# SCH.net
KiCad netlist of a schematic drawn in Altium Designer
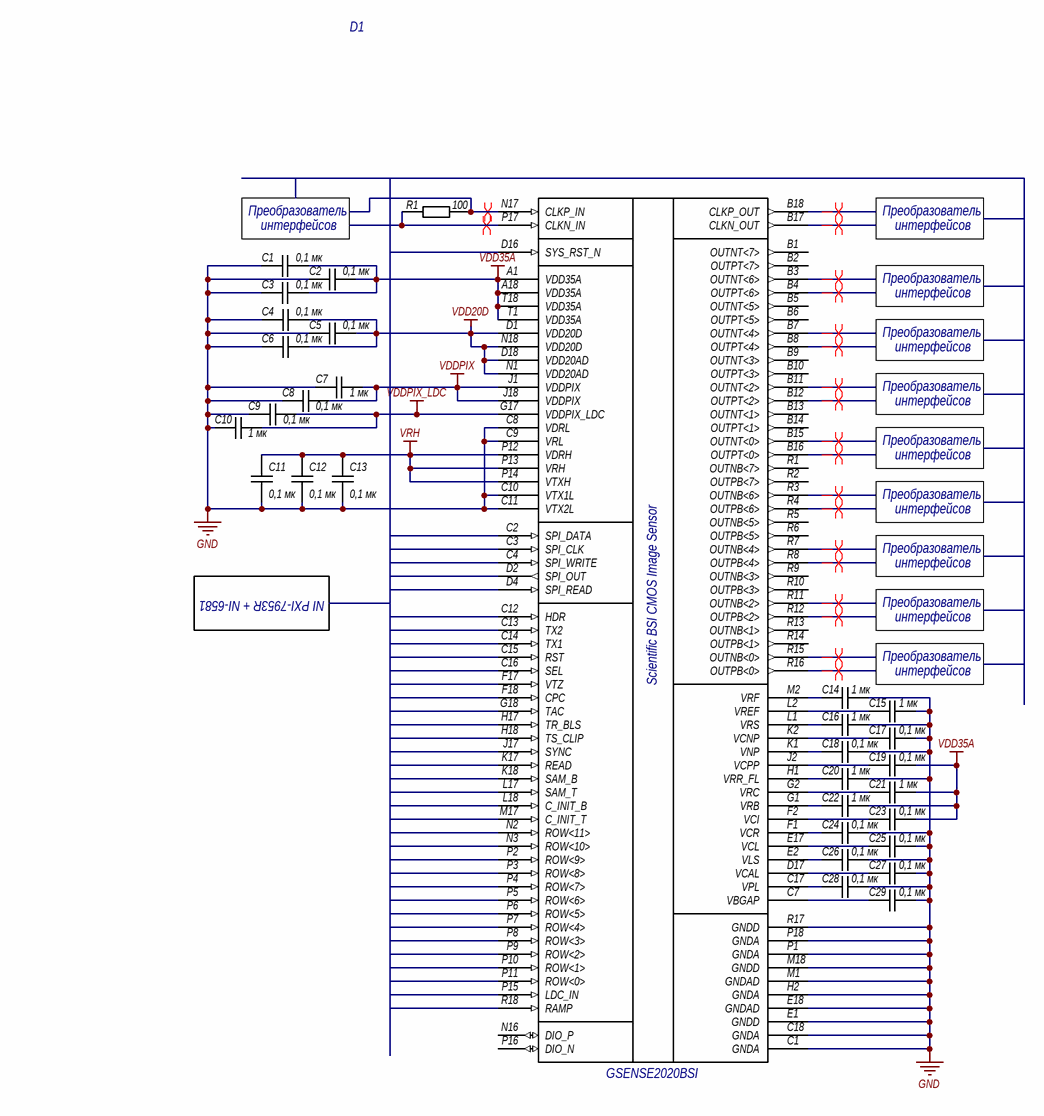
[diagram p0: SCH.SchDoc]

(export (version "E")
  (design (tool "Eeschema 10.0.6"))
  (components
    (comp (ref "C1") (value "0,1 мк") (description "Capacitor") (libsource (lib "VPL") (part "Cap")))
    (comp (ref "C2") (value "0,1 мк") (description "Capacitor") (libsource (lib "VPL") (part "Cap")))
    (comp (ref "C3") (value "0,1 мк") (description "Capacitor") (libsource (lib "VPL") (part "Cap")))
    (comp (ref "C4") (value "0,1 мк") (description "Capacitor") (libsource (lib "VPL") (part "Cap")))
    (comp (ref "C5") (value "0,1 мк") (description "Capacitor") (libsource (lib "VPL") (part "Cap")))
    (comp (ref "C6") (value "0,1 мк") (description "Capacitor") (libsource (lib "VPL") (part "Cap")))
    (comp (ref "C7") (value "1 мк") (description "Capacitor") (libsource (lib "VPL") (part "Cap")))
    (comp (ref "C8") (value "0,1 мк") (description "Capacitor") (libsource (lib "VPL") (part "Cap")))
    (comp (ref "C9") (value "0,1 мк") (description "Capacitor") (libsource (lib "VPL") (part "Cap")))
    (comp (ref "C10") (value "1 мк") (description "Capacitor") (libsource (lib "VPL") (part "Cap")))
    (comp (ref "C11") (value "0,1 мк") (description "Capacitor") (libsource (lib "VPL") (part "Cap")))
    (comp (ref "C12") (value "0,1 мк") (description "Capacitor") (libsource (lib "VPL") (part "Cap")))
    (comp (ref "C13") (value "0,1 мк") (description "Capacitor") (libsource (lib "VPL") (part "Cap")))
    (comp (ref "C14") (value "1 мк") (description "Capacitor") (libsource (lib "VPL") (part "Cap")))
    (comp (ref "C15") (value "1 мк") (description "Capacitor") (libsource (lib "VPL") (part "Cap")))
    (comp (ref "C16") (value "1 мк") (description "Capacitor") (libsource (lib "VPL") (part "Cap")))
    (comp (ref "C17") (value "0,1 мк") (description "Capacitor") (libsource (lib "VPL") (part "Cap")))
    (comp (ref "C18") (value "0,1 мк") (description "Capacitor") (libsource (lib "VPL") (part "Cap")))
    (comp (ref "C19") (value "0,1 мк") (description "Capacitor") (libsource (lib "VPL") (part "Cap")))
    (comp (ref "C20") (value "1 мк") (description "Capacitor") (libsource (lib "VPL") (part "Cap")))
    (comp (ref "C21") (value "1 мк") (description "Capacitor") (libsource (lib "VPL") (part "Cap")))
    (comp (ref "C22") (value "1 мк") (description "Capacitor") (libsource (lib "VPL") (part "Cap")))
    (comp (ref "C23") (value "0,1 мк") (description "Capacitor") (libsource (lib "VPL") (part "Cap")))
    (comp (ref "C24") (value "0,1 мк") (description "Capacitor") (libsource (lib "VPL") (part "Cap")))
    (comp (ref "C25") (value "0,1 мк") (description "Capacitor") (libsource (lib "VPL") (part "Cap")))
    (comp (ref "C26") (value "0,1 мк") (description "Capacitor") (libsource (lib "VPL") (part "Cap")))
    (comp (ref "C27") (value "0,1 мк") (description "Capacitor") (libsource (lib "VPL") (part "Cap")))
    (comp (ref "C28") (value "0,1 мк") (description "Capacitor") (libsource (lib "VPL") (part "Cap")))
    (comp (ref "C29") (value "0,1 мк") (description "Capacitor") (libsource (lib "VPL") (part "Cap")))
    (comp (ref "D1")
      (value "GSENSE2020BSI")
      (footprint "GSENSE2020BSI")
      (libsource (lib "Schlib") (part "GSENSE2020BSI"))
    )
    (comp (ref "R1")
      (value "100")
      (footprint "RES")
      (description "Resistor")
      (libsource (lib "VPL") (part "Res"))
    )
  )
  (nets
    (net (code "1") (name "GND") (class "Default")
      (node (ref "C1") (pin "2") (pintype "passive"))
      (node (ref "C10") (pin "2") (pintype "passive"))
      (node (ref "C11") (pin "1") (pintype "passive"))
      (node (ref "C12") (pin "1") (pintype "passive"))
      (node (ref "C13") (pin "1") (pintype "passive"))
      (node (ref "C14") (pin "2") (pintype "passive"))
      (node (ref "C15") (pin "2") (pintype "passive"))
      (node (ref "C16") (pin "2") (pintype "passive"))
      (node (ref "C17") (pin "2") (pintype "passive"))
      (node (ref "C18") (pin "2") (pintype "passive"))
      (node (ref "C2") (pin "2") (pintype "passive"))
      (node (ref "C20") (pin "2") (pintype "passive"))
      (node (ref "C24") (pin "2") (pintype "passive"))
      (node (ref "C25") (pin "2") (pintype "passive"))
      (node (ref "C26") (pin "2") (pintype "passive"))
      (node (ref "C27") (pin "2") (pintype "passive"))
      (node (ref "C28") (pin "2") (pintype "passive"))
      (node (ref "C29") (pin "2") (pintype "passive"))
      (node (ref "C3") (pin "2") (pintype "passive"))
      (node (ref "C4") (pin "2") (pintype "passive"))
      (node (ref "C5") (pin "2") (pintype "passive"))
      (node (ref "C6") (pin "2") (pintype "passive"))
      (node (ref "C7") (pin "2") (pintype "passive"))
      (node (ref "C8") (pin "2") (pintype "passive"))
      (node (ref "C9") (pin "2") (pintype "passive"))
      (node (ref "D1") (pin "C1") (pinfunction "GNDA_C1") (pintype "passive"))
      (node (ref "D1") (pin "C10") (pinfunction "VTX1L_C10") (pintype "passive"))
      (node (ref "D1") (pin "C11") (pinfunction "VTX2L_C11") (pintype "passive"))
      (node (ref "D1") (pin "C18") (pinfunction "GNDA_C18") (pintype "passive"))
      (node (ref "D1") (pin "C8") (pinfunction "VDRL_C8") (pintype "passive"))
      (node (ref "D1") (pin "C9") (pinfunction "VRL_C9") (pintype "passive"))
      (node (ref "D1") (pin "E1") (pinfunction "GNDD_E1") (pintype "passive"))
      (node (ref "D1") (pin "E18") (pinfunction "GNDAD_E18") (pintype "passive"))
      (node (ref "D1") (pin "H2") (pinfunction "GNDA_H2") (pintype "passive"))
      (node (ref "D1") (pin "M1") (pinfunction "GNDAD_M1") (pintype "passive"))
      (node (ref "D1") (pin "M18") (pinfunction "GNDD_M18") (pintype "passive"))
      (node (ref "D1") (pin "P1") (pinfunction "GNDA_P1") (pintype "passive"))
      (node (ref "D1") (pin "P18") (pinfunction "GNDA_P18") (pintype "passive"))
      (node (ref "D1") (pin "R17") (pinfunction "GNDD_R17") (pintype "passive"))
    )
    (net (code "2") (name "Net-(D1-CLKN_IN)") (class "Default")
      (node (ref "D1") (pin "P17") (pinfunction "CLKN_IN_P17") (pintype "input"))
      (node (ref "R1") (pin "2") (pintype "passive"))
    )
    (net (code "3") (name "Net-(D1-CLKP_IN)") (class "Default")
      (node (ref "D1") (pin "N17") (pinfunction "CLKP_IN_N17") (pintype "input"))
      (node (ref "R1") (pin "1") (pintype "passive"))
    )
    (net (code "4") (name "Net-(D1-VBGAP)") (class "Default")
      (node (ref "C29") (pin "1") (pintype "passive"))
      (node (ref "D1") (pin "C7") (pinfunction "VBGAP_C7") (pintype "passive"))
    )
    (net (code "5") (name "Net-(D1-VCAL)") (class "Default")
      (node (ref "C27") (pin "1") (pintype "passive"))
      (node (ref "D1") (pin "D17") (pinfunction "VCAL_D17") (pintype "passive"))
    )
    (net (code "6") (name "Net-(D1-VCI)") (class "Default")
      (node (ref "C23") (pin "1") (pintype "passive"))
      (node (ref "D1") (pin "F2") (pinfunction "VCI_F2") (pintype "passive"))
    )
    (net (code "7") (name "Net-(D1-VCL)") (class "Default")
      (node (ref "C25") (pin "1") (pintype "passive"))
      (node (ref "D1") (pin "E17") (pinfunction "VCL_E17") (pintype "passive"))
    )
    (net (code "8") (name "Net-(D1-VCNP)") (class "Default")
      (node (ref "C17") (pin "1") (pintype "passive"))
      (node (ref "D1") (pin "K2") (pinfunction "VCNP_K2") (pintype "passive"))
    )
    (net (code "9") (name "Net-(D1-VCPP)") (class "Default")
      (node (ref "C19") (pin "1") (pintype "passive"))
      (node (ref "D1") (pin "J2") (pinfunction "VCPP_J2") (pintype "passive"))
    )
    (net (code "10") (name "Net-(D1-VCR)") (class "Default")
      (node (ref "C24") (pin "1") (pintype "passive"))
      (node (ref "D1") (pin "F1") (pinfunction "VCR_F1") (pintype "passive"))
    )
    (net (code "11") (name "Net-(D1-VLS)") (class "Default")
      (node (ref "C26") (pin "1") (pintype "passive"))
      (node (ref "D1") (pin "E2") (pinfunction "VLS_E2") (pintype "passive"))
    )
    (net (code "12") (name "Net-(D1-VNP)") (class "Default")
      (node (ref "C18") (pin "1") (pintype "passive"))
      (node (ref "D1") (pin "K1") (pinfunction "VNP_K1") (pintype "passive"))
    )
    (net (code "13") (name "Net-(D1-VPL)") (class "Default")
      (node (ref "C28") (pin "1") (pintype "passive"))
      (node (ref "D1") (pin "C17") (pinfunction "VPL_C17") (pintype "passive"))
    )
    (net (code "14") (name "Net-(D1-VRB)") (class "Default")
      (node (ref "C22") (pin "1") (pintype "passive"))
      (node (ref "D1") (pin "G1") (pinfunction "VRB_G1") (pintype "passive"))
    )
    (net (code "15") (name "Net-(D1-VRC)") (class "Default")
      (node (ref "C21") (pin "1") (pintype "passive"))
      (node (ref "D1") (pin "G2") (pinfunction "VRC_G2") (pintype "passive"))
    )
    (net (code "16") (name "Net-(D1-VREF)") (class "Default")
      (node (ref "C15") (pin "1") (pintype "passive"))
      (node (ref "D1") (pin "L2") (pinfunction "VREF_L2") (pintype "passive"))
    )
    (net (code "17") (name "Net-(D1-VRF)") (class "Default")
      (node (ref "C14") (pin "1") (pintype "passive"))
      (node (ref "D1") (pin "M2") (pinfunction "VRF_M2") (pintype "passive"))
    )
    (net (code "18") (name "Net-(D1-VRR_FL)") (class "Default")
      (node (ref "C20") (pin "1") (pintype "passive"))
      (node (ref "D1") (pin "H1") (pinfunction "VRR_FL_H1") (pintype "passive"))
    )
    (net (code "19") (name "Net-(D1-VRS)") (class "Default")
      (node (ref "C16") (pin "1") (pintype "passive"))
      (node (ref "D1") (pin "L1") (pinfunction "VRS_L1") (pintype "passive"))
    )
    (net (code "20") (name "VDD20D") (class "Default")
      (node (ref "C4") (pin "1") (pintype "passive"))
      (node (ref "C5") (pin "1") (pintype "passive"))
      (node (ref "C6") (pin "1") (pintype "passive"))
      (node (ref "D1") (pin "D1") (pinfunction "VDD20D_D1") (pintype "passive"))
      (node (ref "D1") (pin "D18") (pinfunction "VDD20AD_D18") (pintype "passive"))
      (node (ref "D1") (pin "N1") (pinfunction "VDD20AD_N1") (pintype "passive"))
      (node (ref "D1") (pin "N18") (pinfunction "VDD20D_N18") (pintype "passive"))
    )
    (net (code "21") (name "VDD35A") (class "Default")
      (node (ref "C1") (pin "1") (pintype "passive"))
      (node (ref "C19") (pin "2") (pintype "passive"))
      (node (ref "C2") (pin "1") (pintype "passive"))
      (node (ref "C21") (pin "2") (pintype "passive"))
      (node (ref "C22") (pin "2") (pintype "passive"))
      (node (ref "C23") (pin "2") (pintype "passive"))
      (node (ref "C3") (pin "1") (pintype "passive"))
      (node (ref "D1") (pin "A1") (pinfunction "VDD35A_A1") (pintype "passive"))
      (node (ref "D1") (pin "A18") (pinfunction "VDD35A_A18") (pintype "passive"))
      (node (ref "D1") (pin "T1") (pinfunction "VDD35A_T1") (pintype "passive"))
      (node (ref "D1") (pin "T18") (pinfunction "VDD35A_T18") (pintype "passive"))
    )
    (net (code "22") (name "VDDPIX") (class "Default")
      (node (ref "C7") (pin "1") (pintype "passive"))
      (node (ref "C8") (pin "1") (pintype "passive"))
      (node (ref "D1") (pin "J1") (pinfunction "VDDPIX_J1") (pintype "passive"))
      (node (ref "D1") (pin "J18") (pinfunction "VDDPIX_J18") (pintype "passive"))
    )
    (net (code "23") (name "VDDPIX_LDC") (class "Default")
      (node (ref "C10") (pin "1") (pintype "passive"))
      (node (ref "C9") (pin "1") (pintype "passive"))
      (node (ref "D1") (pin "G17") (pinfunction "VDDPIX_LDC_G17") (pintype "passive"))
    )
    (net (code "24") (name "VRH") (class "Default")
      (node (ref "C11") (pin "2") (pintype "passive"))
      (node (ref "C12") (pin "2") (pintype "passive"))
      (node (ref "C13") (pin "2") (pintype "passive"))
      (node (ref "D1") (pin "P12") (pinfunction "VDRH_P12") (pintype "passive"))
      (node (ref "D1") (pin "P13") (pinfunction "VRH_P13") (pintype "passive"))
      (node (ref "D1") (pin "P14") (pinfunction "VTXH_P14") (pintype "passive"))
    )
    (net (code "25") (name "unconnected-(D1-CLKN_OUT-PadB17)") (class "Default")
      (node (ref "D1") (pin "B17") (pinfunction "CLKN_OUT_B17") (pintype "output"))
    )
    (net (code "26") (name "unconnected-(D1-CLKP_OUT-PadB18)") (class "Default")
      (node (ref "D1") (pin "B18") (pinfunction "CLKP_OUT_B18") (pintype "output"))
    )
    (net (code "27") (name "unconnected-(D1-CPC-PadF18)") (class "Default")
      (node (ref "D1") (pin "F18") (pinfunction "CPC_F18") (pintype "input"))
    )
    (net (code "28") (name "unconnected-(D1-C_INIT_B-PadL18)") (class "Default")
      (node (ref "D1") (pin "L18") (pinfunction "C_INIT_B_L18") (pintype "input"))
    )
    (net (code "29") (name "unconnected-(D1-C_INIT_T-PadM17)") (class "Default")
      (node (ref "D1") (pin "M17") (pinfunction "C_INIT_T_M17") (pintype "input"))
    )
    (net (code "30") (name "unconnected-(D1-DIO_N-PadP16)") (class "Default")
      (node (ref "D1") (pin "P16") (pinfunction "DIO_N_P16") (pintype "bidirectional"))
    )
    (net (code "31") (name "unconnected-(D1-DIO_P-PadN16)") (class "Default")
      (node (ref "D1") (pin "N16") (pinfunction "DIO_P_N16") (pintype "bidirectional"))
    )
    (net (code "32") (name "unconnected-(D1-HDR-PadC12)") (class "Default")
      (node (ref "D1") (pin "C12") (pinfunction "HDR_C12") (pintype "input"))
    )
    (net (code "33") (name "unconnected-(D1-LDC_IN-PadP15)") (class "Default")
      (node (ref "D1") (pin "P15") (pinfunction "LDC_IN_P15") (pintype "input"))
    )
    (net (code "34") (name "unconnected-(D1-OUTNB<0>-PadR15)") (class "Default")
      (node (ref "D1") (pin "R15") (pinfunction "OUTNB<0>_R15") (pintype "output"))
    )
    (net (code "35") (name "unconnected-(D1-OUTNB<1>-PadR13)") (class "Default")
      (node (ref "D1") (pin "R13") (pinfunction "OUTNB<1>_R13") (pintype "output"))
    )
    (net (code "36") (name "unconnected-(D1-OUTNB<2>-PadR11)") (class "Default")
      (node (ref "D1") (pin "R11") (pinfunction "OUTNB<2>_R11") (pintype "output"))
    )
    (net (code "37") (name "unconnected-(D1-OUTNB<3>-PadR9)") (class "Default")
      (node (ref "D1") (pin "R9") (pinfunction "OUTNB<3>_R9") (pintype "output"))
    )
    (net (code "38") (name "unconnected-(D1-OUTNB<4>-PadR7)") (class "Default")
      (node (ref "D1") (pin "R7") (pinfunction "OUTNB<4>_R7") (pintype "output"))
    )
    (net (code "39") (name "unconnected-(D1-OUTNB<5>-PadR5)") (class "Default")
      (node (ref "D1") (pin "R5") (pinfunction "OUTNB<5>_R5") (pintype "output"))
    )
    (net (code "40") (name "unconnected-(D1-OUTNB<6>-PadR3)") (class "Default")
      (node (ref "D1") (pin "R3") (pinfunction "OUTNB<6>_R3") (pintype "output"))
    )
    (net (code "41") (name "unconnected-(D1-OUTNB<7>-PadR1)") (class "Default")
      (node (ref "D1") (pin "R1") (pinfunction "OUTNB<7>_R1") (pintype "output"))
    )
    (net (code "42") (name "unconnected-(D1-OUTNT<0>-PadB15)") (class "Default")
      (node (ref "D1") (pin "B15") (pinfunction "OUTNT<0>_B15") (pintype "output"))
    )
    (net (code "43") (name "unconnected-(D1-OUTNT<1>-PadB13)") (class "Default")
      (node (ref "D1") (pin "B13") (pinfunction "OUTNT<1>_B13") (pintype "output"))
    )
    (net (code "44") (name "unconnected-(D1-OUTNT<2>-PadB11)") (class "Default")
      (node (ref "D1") (pin "B11") (pinfunction "OUTNT<2>_B11") (pintype "output"))
    )
    (net (code "45") (name "unconnected-(D1-OUTNT<3>-PadB9)") (class "Default")
      (node (ref "D1") (pin "B9") (pinfunction "OUTNT<3>_B9") (pintype "output"))
    )
    (net (code "46") (name "unconnected-(D1-OUTNT<4>-PadB7)") (class "Default")
      (node (ref "D1") (pin "B7") (pinfunction "OUTNT<4>_B7") (pintype "output"))
    )
    (net (code "47") (name "unconnected-(D1-OUTNT<5>-PadB5)") (class "Default")
      (node (ref "D1") (pin "B5") (pinfunction "OUTNT<5>_B5") (pintype "output"))
    )
    (net (code "48") (name "unconnected-(D1-OUTNT<6>-PadB3)") (class "Default")
      (node (ref "D1") (pin "B3") (pinfunction "OUTNT<6>_B3") (pintype "output"))
    )
    (net (code "49") (name "unconnected-(D1-OUTNT<7>-PadB1)") (class "Default")
      (node (ref "D1") (pin "B1") (pinfunction "OUTNT<7>_B1") (pintype "output"))
    )
    (net (code "50") (name "unconnected-(D1-OUTPB<0>-PadR16)") (class "Default")
      (node (ref "D1") (pin "R16") (pinfunction "OUTPB<0>_R16") (pintype "output"))
    )
    (net (code "51") (name "unconnected-(D1-OUTPB<1>-PadR14)") (class "Default")
      (node (ref "D1") (pin "R14") (pinfunction "OUTPB<1>_R14") (pintype "output"))
    )
    (net (code "52") (name "unconnected-(D1-OUTPB<2>-PadR12)") (class "Default")
      (node (ref "D1") (pin "R12") (pinfunction "OUTPB<2>_R12") (pintype "output"))
    )
    (net (code "53") (name "unconnected-(D1-OUTPB<3>-PadR10)") (class "Default")
      (node (ref "D1") (pin "R10") (pinfunction "OUTPB<3>_R10") (pintype "output"))
    )
    (net (code "54") (name "unconnected-(D1-OUTPB<4>-PadR8)") (class "Default")
      (node (ref "D1") (pin "R8") (pinfunction "OUTPB<4>_R8") (pintype "output"))
    )
    (net (code "55") (name "unconnected-(D1-OUTPB<5>-PadR6)") (class "Default")
      (node (ref "D1") (pin "R6") (pinfunction "OUTPB<5>_R6") (pintype "output"))
    )
    (net (code "56") (name "unconnected-(D1-OUTPB<6>-PadR4)") (class "Default")
      (node (ref "D1") (pin "R4") (pinfunction "OUTPB<6>_R4") (pintype "output"))
    )
    (net (code "57") (name "unconnected-(D1-OUTPB<7>-PadR2)") (class "Default")
      (node (ref "D1") (pin "R2") (pinfunction "OUTPB<7>_R2") (pintype "output"))
    )
    (net (code "58") (name "unconnected-(D1-OUTPT<0>-PadB16)") (class "Default")
      (node (ref "D1") (pin "B16") (pinfunction "OUTPT<0>_B16") (pintype "output"))
    )
    (net (code "59") (name "unconnected-(D1-OUTPT<1>-PadB14)") (class "Default")
      (node (ref "D1") (pin "B14") (pinfunction "OUTPT<1>_B14") (pintype "output"))
    )
    (net (code "60") (name "unconnected-(D1-OUTPT<2>-PadB12)") (class "Default")
      (node (ref "D1") (pin "B12") (pinfunction "OUTPT<2>_B12") (pintype "output"))
    )
    (net (code "61") (name "unconnected-(D1-OUTPT<3>-PadB10)") (class "Default")
      (node (ref "D1") (pin "B10") (pinfunction "OUTPT<3>_B10") (pintype "output"))
    )
    (net (code "62") (name "unconnected-(D1-OUTPT<4>-PadB8)") (class "Default")
      (node (ref "D1") (pin "B8") (pinfunction "OUTPT<4>_B8") (pintype "output"))
    )
    (net (code "63") (name "unconnected-(D1-OUTPT<5>-PadB6)") (class "Default")
      (node (ref "D1") (pin "B6") (pinfunction "OUTPT<5>_B6") (pintype "output"))
    )
    (net (code "64") (name "unconnected-(D1-OUTPT<6>-PadB4)") (class "Default")
      (node (ref "D1") (pin "B4") (pinfunction "OUTPT<6>_B4") (pintype "output"))
    )
    (net (code "65") (name "unconnected-(D1-OUTPT<7>-PadB2)") (class "Default")
      (node (ref "D1") (pin "B2") (pinfunction "OUTPT<7>_B2") (pintype "output"))
    )
    (net (code "66") (name "unconnected-(D1-RAMP-PadR18)") (class "Default")
      (node (ref "D1") (pin "R18") (pinfunction "RAMP_R18") (pintype "input"))
    )
    (net (code "67") (name "unconnected-(D1-READ-PadK17)") (class "Default")
      (node (ref "D1") (pin "K17") (pinfunction "READ_K17") (pintype "input"))
    )
    (net (code "68") (name "unconnected-(D1-ROW<0>-PadP11)") (class "Default")
      (node (ref "D1") (pin "P11") (pinfunction "ROW<0>_P11") (pintype "input"))
    )
    (net (code "69") (name "unconnected-(D1-ROW<1>-PadP10)") (class "Default")
      (node (ref "D1") (pin "P10") (pinfunction "ROW<1>_P10") (pintype "input"))
    )
    (net (code "70") (name "unconnected-(D1-ROW<2>-PadP9)") (class "Default")
      (node (ref "D1") (pin "P9") (pinfunction "ROW<2>_P9") (pintype "input"))
    )
    (net (code "71") (name "unconnected-(D1-ROW<3>-PadP8)") (class "Default")
      (node (ref "D1") (pin "P8") (pinfunction "ROW<3>_P8") (pintype "input"))
    )
    (net (code "72") (name "unconnected-(D1-ROW<4>-PadP7)") (class "Default")
      (node (ref "D1") (pin "P7") (pinfunction "ROW<4>_P7") (pintype "input"))
    )
    (net (code "73") (name "unconnected-(D1-ROW<5>-PadP6)") (class "Default")
      (node (ref "D1") (pin "P6") (pinfunction "ROW<5>_P6") (pintype "input"))
    )
    (net (code "74") (name "unconnected-(D1-ROW<6>-PadP5)") (class "Default")
      (node (ref "D1") (pin "P5") (pinfunction "ROW<6>_P5") (pintype "input"))
    )
    (net (code "75") (name "unconnected-(D1-ROW<7>-PadP4)") (class "Default")
      (node (ref "D1") (pin "P4") (pinfunction "ROW<7>_P4") (pintype "input"))
    )
    (net (code "76") (name "unconnected-(D1-ROW<8>-PadP3)") (class "Default")
      (node (ref "D1") (pin "P3") (pinfunction "ROW<8>_P3") (pintype "input"))
    )
    (net (code "77") (name "unconnected-(D1-ROW<9>-PadP2)") (class "Default")
      (node (ref "D1") (pin "P2") (pinfunction "ROW<9>_P2") (pintype "input"))
    )
    (net (code "78") (name "unconnected-(D1-ROW<10>-PadN3)") (class "Default")
      (node (ref "D1") (pin "N3") (pinfunction "ROW<10>_N3") (pintype "input"))
    )
    (net (code "79") (name "unconnected-(D1-ROW<11>-PadN2)") (class "Default")
      (node (ref "D1") (pin "N2") (pinfunction "ROW<11>_N2") (pintype "input"))
    )
    (net (code "80") (name "unconnected-(D1-RST-PadC15)") (class "Default")
      (node (ref "D1") (pin "C15") (pinfunction "RST_C15") (pintype "input"))
    )
    (net (code "81") (name "unconnected-(D1-SAM_B-PadK18)") (class "Default")
      (node (ref "D1") (pin "K18") (pinfunction "SAM_B_K18") (pintype "input"))
    )
    (net (code "82") (name "unconnected-(D1-SAM_T-PadL17)") (class "Default")
      (node (ref "D1") (pin "L17") (pinfunction "SAM_T_L17") (pintype "input"))
    )
    (net (code "83") (name "unconnected-(D1-SEL-PadC16)") (class "Default")
      (node (ref "D1") (pin "C16") (pinfunction "SEL_C16") (pintype "input"))
    )
    (net (code "84") (name "unconnected-(D1-SPI_CLK-PadC3)") (class "Default")
      (node (ref "D1") (pin "C3") (pinfunction "SPI_CLK_C3") (pintype "input"))
    )
    (net (code "85") (name "unconnected-(D1-SPI_DATA-PadC2)") (class "Default")
      (node (ref "D1") (pin "C2") (pinfunction "SPI_DATA_C2") (pintype "input"))
    )
    (net (code "86") (name "unconnected-(D1-SPI_OUT-PadD2)") (class "Default")
      (node (ref "D1") (pin "D2") (pinfunction "SPI_OUT_D2") (pintype "output"))
    )
    (net (code "87") (name "unconnected-(D1-SPI_READ-PadD4)") (class "Default")
      (node (ref "D1") (pin "D4") (pinfunction "SPI_READ_D4") (pintype "input"))
    )
    (net (code "88") (name "unconnected-(D1-SPI_WRITE-PadC4)") (class "Default")
      (node (ref "D1") (pin "C4") (pinfunction "SPI_WRITE_C4") (pintype "input"))
    )
    (net (code "89") (name "unconnected-(D1-SYNC-PadJ17)") (class "Default")
      (node (ref "D1") (pin "J17") (pinfunction "SYNC_J17") (pintype "input"))
    )
    (net (code "90") (name "unconnected-(D1-SYS_RST_N-PadD16)") (class "Default")
      (node (ref "D1") (pin "D16") (pinfunction "SYS_RST_N_D16") (pintype "input"))
    )
    (net (code "91") (name "unconnected-(D1-TAC-PadG18)") (class "Default")
      (node (ref "D1") (pin "G18") (pinfunction "TAC_G18") (pintype "input"))
    )
    (net (code "92") (name "unconnected-(D1-TR_BLS-PadH17)") (class "Default")
      (node (ref "D1") (pin "H17") (pinfunction "TR_BLS_H17") (pintype "input"))
    )
    (net (code "93") (name "unconnected-(D1-TS_CLIP-PadH18)") (class "Default")
      (node (ref "D1") (pin "H18") (pinfunction "TS_CLIP_H18") (pintype "input"))
    )
    (net (code "94") (name "unconnected-(D1-TX1-PadC14)") (class "Default")
      (node (ref "D1") (pin "C14") (pinfunction "TX1_C14") (pintype "input"))
    )
    (net (code "95") (name "unconnected-(D1-TX2-PadC13)") (class "Default")
      (node (ref "D1") (pin "C13") (pinfunction "TX2_C13") (pintype "input"))
    )
    (net (code "96") (name "unconnected-(D1-VTZ-PadF17)") (class "Default")
      (node (ref "D1") (pin "F17") (pinfunction "VTZ_F17") (pintype "input"))
    )
  )
)
